# CAN_IF.net
KiCad netlist of a schematic drawn in Altium Designer
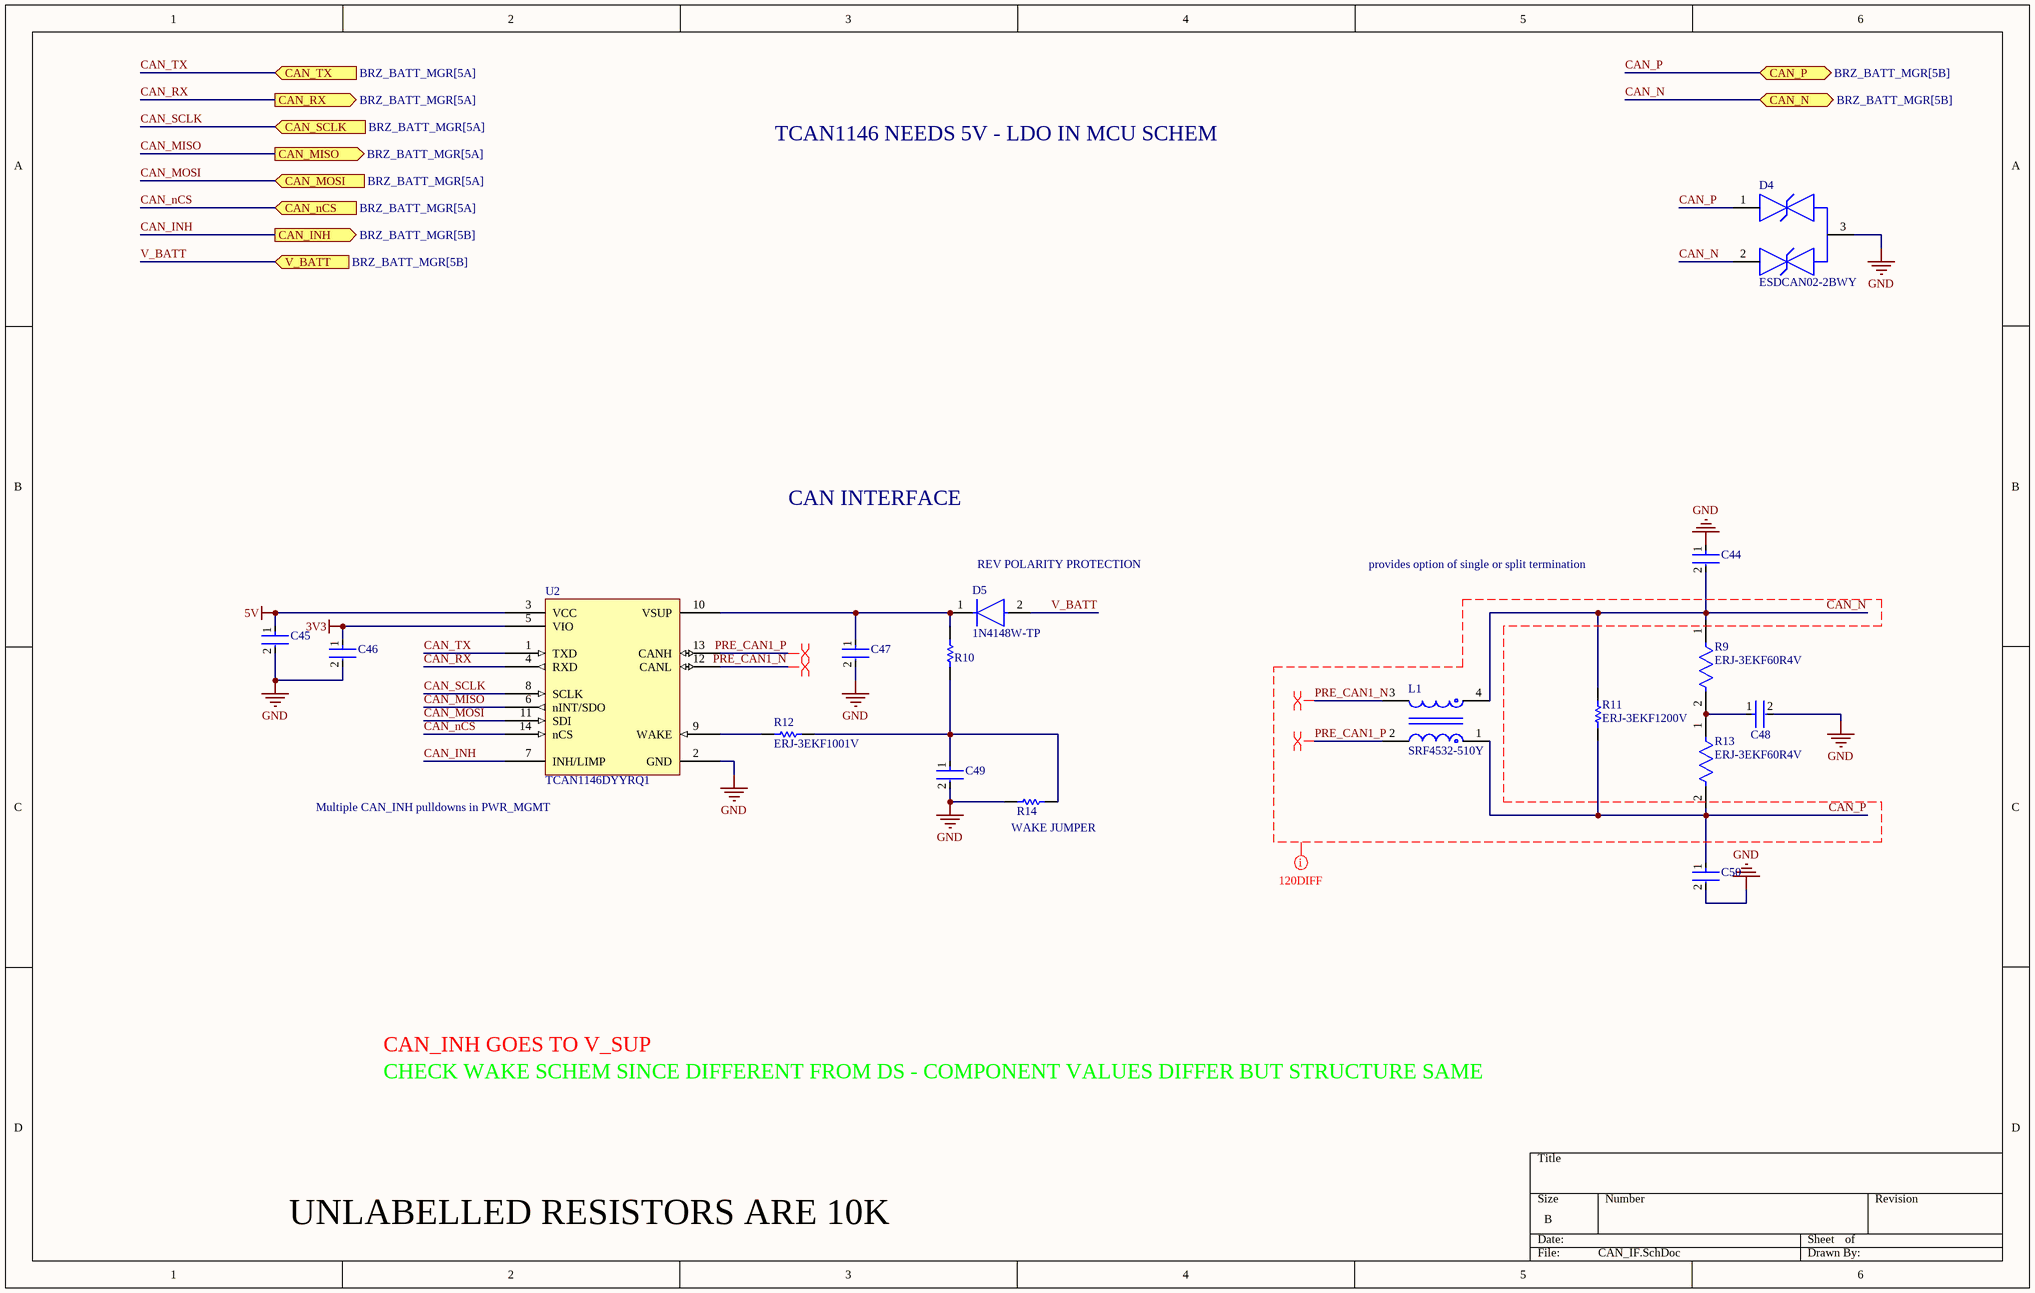
[diagram p0: CAN_IF.SchDoc]

(export (version "E")
  (design (tool "Eeschema 10.0.6"))
  (components
    (comp (ref "C44")
      (value "DNO")
      (footprint "FP-0402-L_1_0_0_05-W_0_5-IPC_A")
      (description "LARGE PADS, 0402 CAP, CHANGE COMMENT TO MATCH REAL P/N")
      (libsource (lib "Space Concordia") (part "b4654b650e69147ec39a6b967a45e02"))
    )
    (comp (ref "C45")
      (value "GRM188R71H104KA93D")
      (footprint "FP-0402-L_1_0_0_05-W_0_5-IPC_A")
      (description "LARGE PADS, 0402 CAP, CHANGE COMMENT TO MATCH REAL P/N")
      (libsource (lib "Space Concordia") (part "b4654b650e69147ec39a6b967a45e02"))
    )
    (comp (ref "C46")
      (value "GRM188R71H104KA93D")
      (footprint "FP-0402-L_1_0_0_05-W_0_5-IPC_A")
      (description "LARGE PADS, 0402 CAP, CHANGE COMMENT TO MATCH REAL P/N")
      (libsource (lib "Space Concordia") (part "b4654b650e69147ec39a6b967a45e02"))
    )
    (comp (ref "C47")
      (value "GRM188R71H104KA93D")
      (footprint "FP-0402-L_1_0_0_05-W_0_5-IPC_A")
      (description "LARGE PADS, 0402 CAP, CHANGE COMMENT TO MATCH REAL P/N")
      (libsource (lib "Space Concordia") (part "b4654b650e69147ec39a6b967a45e02"))
    )
    (comp (ref "C48")
      (value "GRM188R71H104KA93D")
      (footprint "FP-0402-L_1_0_0_05-W_0_5-IPC_A")
      (description "LARGE PADS, 0402 CAP, CHANGE COMMENT TO MATCH REAL P/N")
      (libsource (lib "Space Concordia") (part "b4654b650e69147ec39a6b967a45e02"))
    )
    (comp (ref "C49")
      (value "GRM188R71H104KA93D")
      (footprint "FP-0402-L_1_0_0_05-W_0_5-IPC_A")
      (description "LARGE PADS, 0402 CAP, CHANGE COMMENT TO MATCH REAL P/N")
      (libsource (lib "Space Concordia") (part "b4654b650e69147ec39a6b967a45e02"))
    )
    (comp (ref "C50")
      (value "DNO")
      (footprint "FP-0402-L_1_0_0_05-W_0_5-IPC_A")
      (description "LARGE PADS, 0402 CAP, CHANGE COMMENT TO MATCH REAL P/N")
      (libsource (lib "Space Concordia") (part "b4654b650e69147ec39a6b967a45e02"))
    )
    (comp (ref "D4")
      (value "ESDCAN02-2BWY")
      (footprint "FP-SOT323-3L-MFG")
      (description "TVS DIODE 26.5V 44V SOT323-3")
      (fields
        (field (name "MANUFACTURER") "STMicroelectronics")
        (field (name "OCTOPART") "https://octopart.com/esdcan02-2bwy-stmicroelectronics-58631133")
      )
      (libsource (lib "Altium Content Vault") (part "0b9019fb5e52ed66df21ec1535be59d"))
    )
    (comp (ref "D5")
      (value "1N4148W-TP")
      (footprint "FP-SOD-123-IPC_A")
      (description "DIODE GEN PURP 100V 150MA SOD123")
      (libsource (lib "Altium Content Vault") (part "d7152d700b627762746794eb795d46e"))
    )
    (comp (ref "L1")
      (value "SRF4532-510Y")
      (footprint "FP-SRF4532-MFG")
      (description "CMC 51UH 200MA 2LN 2KOHM SMD")
      (fields (field (name "TOLERANCE") "50%"))
      (libsource (lib "Altium Content Vault") (part "aca3f6a10b859f211cca95010157f3b"))
    )
    (comp (ref "R9")
      (value "ERJ-3EKF60R4V")
      (footprint "FP-ERJ3EK-IPC_C")
      (description "RES SMD 60.4 OHM 1% 1/10W 0603")
      (fields (field (name "TOLERANCE") "1%"))
      (libsource (lib "Altium Content Vault") (part "1029c3af85768c4190bb7ad29bc67b5"))
    )
    (comp (ref "R10")
      (value "ERJ3EKF1002V")
      (footprint "RESC1609X55X30LL15T15")
      (description "Chip Resistor, 10 KOhm, +/- 1%, 0.1 W, -55 to 155 degC, 0603 (1608 Metric), RoHS, Tape and Reel")
      (fields (field (name "TOLERANCE") "1%") (field (name "MANUFACTURER") "Panasonic"))
      (libsource (lib "Altium Content Vault") (part "RES-2"))
    )
    (comp (ref "R11")
      (value "ERJ-3EKF1200V")
      (footprint "RESC1609X55X30ML15T15")
      (description "Chip Resistor, 120 Ohm, +/- 1%, 0.1 W, -55 to 155 degC, 0603 (1608 Metric), RoHS, Tape and Reel")
      (fields (field (name "TOLERANCE") "1%") (field (name "MANUFACTURER") "Panasonic"))
      (libsource (lib "Altium Content Vault") (part "RES-2"))
    )
    (comp (ref "R12")
      (value "ERJ-3EKF1001V")
      (footprint "RESC1608X55X30LL15T15")
      (fields (field (name "MANUFACTURER") "Panasonic"))
      (libsource (lib "Altium Content Vault") (part "RES"))
    )
    (comp (ref "R13")
      (value "ERJ-3EKF60R4V")
      (footprint "FP-ERJ3EK-IPC_C")
      (description "RES SMD 60.4 OHM 1% 1/10W 0603")
      (fields (field (name "TOLERANCE") "1%"))
      (libsource (lib "Altium Content Vault") (part "1029c3af85768c4190bb7ad29bc67b5"))
    )
    (comp (ref "R14")
      (value "0402 JUMPER 0 OHM")
      (footprint "RESC1005X40X25NL05T05")
      (description "READ THE NAME")
      (libsource (lib "uORocketry Hardware") (part "RES"))
    )
    (comp (ref "U2")
      (value "TCAN1146DYYRQ1")
      (footprint "TCAN1146DYYRQ1-Footprint-1")
      (libsource (lib "uORocketry Hardware") (part "TCAN1146DYYRQ1"))
    )
  )
  (nets
    (net (code "1") (name "/CAN_INH") (class "Default")
      (node (ref "U2") (pin "7") (pinfunction "INH/LIMP_7") (pintype "passive"))
    )
    (net (code "2") (name "/CAN_MISO") (class "Default")
      (node (ref "U2") (pin "6") (pinfunction "nINT/SDO_6") (pintype "output"))
    )
    (net (code "3") (name "/CAN_MOSI") (class "Default")
      (node (ref "U2") (pin "11") (pinfunction "SDI_11") (pintype "input"))
    )
    (net (code "4") (name "/CAN_N") (class "Default")
      (node (ref "C44") (pin "2") (pinfunction "2_2") (pintype "passive"))
      (node (ref "D4") (pin "2") (pinfunction "2_2") (pintype "passive"))
      (node (ref "L1") (pin "4") (pinfunction "4_4") (pintype "passive"))
      (node (ref "R11") (pin "1") (pinfunction "1_1") (pintype "passive"))
      (node (ref "R9") (pin "1") (pinfunction "1_1") (pintype "passive"))
    )
    (net (code "5") (name "/CAN_P") (class "Default")
      (node (ref "C50") (pin "1") (pinfunction "1_1") (pintype "passive"))
      (node (ref "D4") (pin "1") (pinfunction "1_1") (pintype "passive"))
      (node (ref "L1") (pin "1") (pinfunction "1_1") (pintype "passive"))
      (node (ref "R11") (pin "2") (pinfunction "2_2") (pintype "passive"))
      (node (ref "R13") (pin "2") (pinfunction "2_2") (pintype "passive"))
    )
    (net (code "6") (name "/CAN_RX") (class "Default")
      (node (ref "U2") (pin "4") (pinfunction "RXD_4") (pintype "output"))
    )
    (net (code "7") (name "/CAN_SCLK") (class "Default")
      (node (ref "U2") (pin "8") (pinfunction "SCLK_8") (pintype "input"))
    )
    (net (code "8") (name "/CAN_TX") (class "Default")
      (node (ref "U2") (pin "1") (pinfunction "TXD_1") (pintype "input"))
    )
    (net (code "9") (name "/CAN_nCS") (class "Default")
      (node (ref "U2") (pin "14") (pinfunction "nCS_14") (pintype "input"))
    )
    (net (code "10") (name "/PRE_CAN1_N") (class "Default")
      (node (ref "L1") (pin "3") (pinfunction "3_3") (pintype "passive"))
      (node (ref "U2") (pin "12") (pinfunction "CANL_12") (pintype "bidirectional"))
    )
    (net (code "11") (name "/PRE_CAN1_P") (class "Default")
      (node (ref "L1") (pin "2") (pinfunction "2_2") (pintype "passive"))
      (node (ref "U2") (pin "13") (pinfunction "CANH_13") (pintype "bidirectional"))
    )
    (net (code "12") (name "/V_BATT") (class "Default")
      (node (ref "D5") (pin "2") (pinfunction "A_2") (pintype "passive"))
    )
    (net (code "13") (name "3V3") (class "Default")
      (node (ref "C46") (pin "1") (pinfunction "1_1") (pintype "passive"))
      (node (ref "U2") (pin "5") (pinfunction "VIO_5") (pintype "power_in"))
    )
    (net (code "14") (name "5V") (class "Default")
      (node (ref "C45") (pin "1") (pinfunction "1_1") (pintype "passive"))
      (node (ref "U2") (pin "3") (pinfunction "VCC_3") (pintype "power_in"))
    )
    (net (code "15") (name "GND") (class "Default")
      (node (ref "C44") (pin "1") (pinfunction "1_1") (pintype "passive"))
      (node (ref "C45") (pin "2") (pinfunction "2_2") (pintype "passive"))
      (node (ref "C46") (pin "2") (pinfunction "2_2") (pintype "passive"))
      (node (ref "C47") (pin "2") (pinfunction "2_2") (pintype "passive"))
      (node (ref "C48") (pin "2") (pinfunction "2_2") (pintype "passive"))
      (node (ref "C49") (pin "2") (pinfunction "2_2") (pintype "passive"))
      (node (ref "C50") (pin "2") (pinfunction "2_2") (pintype "passive"))
      (node (ref "D4") (pin "3") (pinfunction "3_3") (pintype "passive"))
      (node (ref "R14") (pin "1") (pinfunction "1_1") (pintype "passive"))
      (node (ref "U2") (pin "2") (pinfunction "GND_2") (pintype "power_in"))
    )
    (net (code "16") (name "Net-(C48-Pad1)") (class "Default")
      (node (ref "C48") (pin "1") (pinfunction "1_1") (pintype "passive"))
      (node (ref "R13") (pin "1") (pinfunction "1_1") (pintype "passive"))
      (node (ref "R9") (pin "2") (pinfunction "2_2") (pintype "passive"))
    )
    (net (code "17") (name "Net-(C49-Pad1)") (class "Default")
      (node (ref "C49") (pin "1") (pinfunction "1_1") (pintype "passive"))
      (node (ref "R10") (pin "2") (pinfunction "2_2") (pintype "passive"))
      (node (ref "R12") (pin "2") (pinfunction "2_2") (pintype "passive"))
      (node (ref "R14") (pin "2") (pinfunction "2_2") (pintype "passive"))
    )
    (net (code "18") (name "Net-(D5-C)") (class "Default")
      (node (ref "C47") (pin "1") (pinfunction "1_1") (pintype "passive"))
      (node (ref "D5") (pin "1") (pinfunction "C_1") (pintype "passive"))
      (node (ref "R10") (pin "1") (pinfunction "1_1") (pintype "passive"))
      (node (ref "U2") (pin "10") (pinfunction "VSUP_10") (pintype "power_in"))
    )
    (net (code "19") (name "Net-(U2-WAKE)") (class "Default")
      (node (ref "R12") (pin "1") (pinfunction "1_1") (pintype "passive"))
      (node (ref "U2") (pin "9") (pinfunction "WAKE_9") (pintype "input"))
    )
  )
)
